# LDR-3.net
KiCad netlist of a schematic drawn in EAGLE
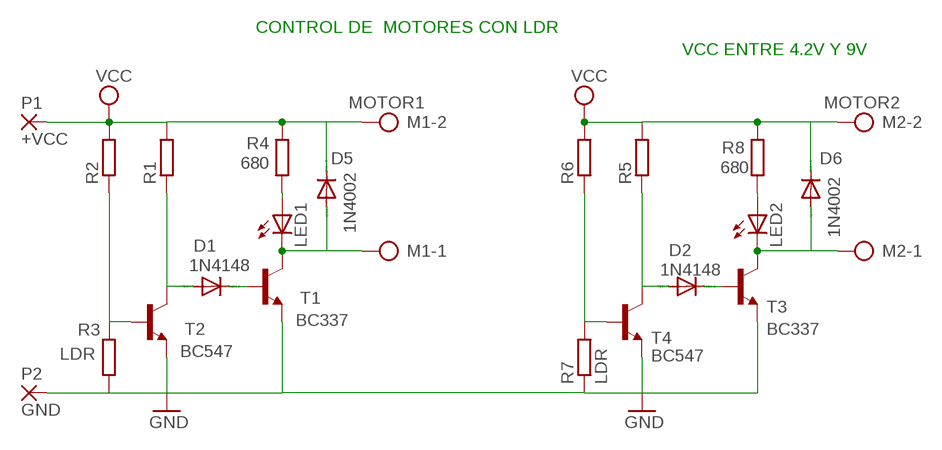
[diagram p0: schematic, sheet 1]

(export (version "E")
  (design (tool "Eeschema 10.0.6"))
  (components
    (comp (ref "D1")
      (value "1N4148")
      (footprint "eagle-import:DO35-7")
      (libsource (lib "eagle-import") (part "1N4148DO35-7"))
    )
    (comp (ref "D2")
      (value "1N4148")
      (footprint "eagle-import:DO35-7")
      (libsource (lib "eagle-import") (part "1N4148DO35-7"))
    )
    (comp (ref "D5")
      (value "1N4002")
      (footprint "eagle-import:DO41-10")
      (libsource (lib "eagle-import") (part "1N4933"))
    )
    (comp (ref "D6")
      (value "1N4002")
      (footprint "eagle-import:DO41-10")
      (libsource (lib "eagle-import") (part "1N4933"))
    )
    (comp (ref "LED1")
      (value "LED3MM")
      (footprint "eagle-import:LED3MM")
      (libsource (lib "eagle-import") (part "LED3MM"))
    )
    (comp (ref "LED2")
      (value "LED3MM")
      (footprint "eagle-import:LED3MM")
      (libsource (lib "eagle-import") (part "LED3MM"))
    )
    (comp (ref "M1")
      (value "MOTOR1")
      (footprint "eagle-import:AK500_2")
      (libsource (lib "eagle-import") (part "AK500/2"))
    )
    (comp (ref "M2")
      (value "MOTOR2")
      (footprint "eagle-import:AK500_2")
      (libsource (lib "eagle-import") (part "AK500/2"))
    )
    (comp (ref "P1")
      (value "+VCC")
      (footprint "eagle-import:2,15_1,0")
      (libsource (lib "eagle-import") (part "WIREPAD2,15/1,0"))
    )
    (comp (ref "P2")
      (value "GND")
      (footprint "eagle-import:2,15_1,0")
      (libsource (lib "eagle-import") (part "WIREPAD2,15/1,0"))
    )
    (comp (ref "R1")
      (value "R-EU_0207/7")
      (footprint "eagle-import:0207_7")
      (libsource (lib "eagle-import") (part "R-EU_0207/7"))
    )
    (comp (ref "R2")
      (value "R-EU_0207/7")
      (footprint "eagle-import:0207_7")
      (libsource (lib "eagle-import") (part "R-EU_0207/7"))
    )
    (comp (ref "R3")
      (value "LDR")
      (footprint "eagle-import:0204_5")
      (libsource (lib "eagle-import") (part "R-EU_0204/5"))
    )
    (comp (ref "R4")
      (value "680")
      (footprint "eagle-import:0207_7")
      (libsource (lib "eagle-import") (part "R-EU_0207/7"))
    )
    (comp (ref "R5")
      (value "R-EU_0207/7")
      (footprint "eagle-import:0207_7")
      (libsource (lib "eagle-import") (part "R-EU_0207/7"))
    )
    (comp (ref "R6")
      (value "R-EU_0207/7")
      (footprint "eagle-import:0207_7")
      (libsource (lib "eagle-import") (part "R-EU_0207/7"))
    )
    (comp (ref "R7")
      (value "LDR")
      (footprint "eagle-import:0204_5")
      (libsource (lib "eagle-import") (part "R-EU_0204/5"))
    )
    (comp (ref "R8")
      (value "680")
      (footprint "eagle-import:0207_7")
      (libsource (lib "eagle-import") (part "R-EU_0207/7"))
    )
    (comp (ref "T1")
      (value "BC337")
      (footprint "eagle-import:TO92-CBE")
      (libsource (lib "eagle-import") (part "-NPN-TO92-CBEBC337-25"))
    )
    (comp (ref "T2")
      (value "BC547")
      (footprint "eagle-import:TO92-CBE")
      (libsource (lib "eagle-import") (part "-NPN-TO92-CBEBC547"))
    )
    (comp (ref "T3")
      (value "BC337")
      (footprint "eagle-import:TO92-CBE")
      (libsource (lib "eagle-import") (part "-NPN-TO92-CBEBC337-25"))
    )
    (comp (ref "T4")
      (value "BC547")
      (footprint "eagle-import:TO92-CBE")
      (libsource (lib "eagle-import") (part "-NPN-TO92-CBEBC547"))
    )
  )
  (nets
    (net (code "1") (name "GND") (class "Default")
      (node (ref "P2") (pin "1") (pinfunction "P_1") (pintype "passive"))
      (node (ref "R3") (pin "1") (pinfunction "1_1") (pintype "passive"))
      (node (ref "R7") (pin "1") (pinfunction "1_1") (pintype "passive"))
      (node (ref "T1") (pin "E") (pinfunction "E_E") (pintype "passive"))
      (node (ref "T2") (pin "E") (pinfunction "E_E") (pintype "passive"))
      (node (ref "T3") (pin "E") (pinfunction "E_E") (pintype "passive"))
      (node (ref "T4") (pin "E") (pinfunction "E_E") (pintype "passive"))
    )
    (net (code "2") (name "Net-(D1-PadA)") (class "Default")
      (node (ref "D1") (pin "A") (pinfunction "A_A") (pintype "passive"))
      (node (ref "R1") (pin "1") (pinfunction "1_1") (pintype "passive"))
      (node (ref "T2") (pin "C") (pinfunction "C_C") (pintype "passive"))
    )
    (net (code "3") (name "Net-(D1-PadC)") (class "Default")
      (node (ref "D1") (pin "C") (pinfunction "C_C") (pintype "passive"))
      (node (ref "T1") (pin "B") (pinfunction "B_B") (pintype "passive"))
    )
    (net (code "4") (name "Net-(D2-PadA)") (class "Default")
      (node (ref "D2") (pin "A") (pinfunction "A_A") (pintype "passive"))
      (node (ref "R5") (pin "1") (pinfunction "1_1") (pintype "passive"))
      (node (ref "T4") (pin "C") (pinfunction "C_C") (pintype "passive"))
    )
    (net (code "5") (name "Net-(D2-PadC)") (class "Default")
      (node (ref "D2") (pin "C") (pinfunction "C_C") (pintype "passive"))
      (node (ref "T3") (pin "B") (pinfunction "B_B") (pintype "passive"))
    )
    (net (code "6") (name "Net-(LED1-C)") (class "Default")
      (node (ref "D5") (pin "A") (pinfunction "A_A") (pintype "passive"))
      (node (ref "LED1") (pin "K") (pinfunction "C_K") (pintype "passive"))
      (node (ref "M1") (pin "1") (pinfunction "KL_1") (pintype "passive"))
      (node (ref "T1") (pin "C") (pinfunction "C_C") (pintype "passive"))
    )
    (net (code "7") (name "Net-(LED1-PadA)") (class "Default")
      (node (ref "LED1") (pin "A") (pinfunction "A_A") (pintype "passive"))
      (node (ref "R4") (pin "1") (pinfunction "1_1") (pintype "passive"))
    )
    (net (code "8") (name "Net-(LED2-C)") (class "Default")
      (node (ref "D6") (pin "A") (pinfunction "A_A") (pintype "passive"))
      (node (ref "LED2") (pin "K") (pinfunction "C_K") (pintype "passive"))
      (node (ref "M2") (pin "1") (pinfunction "KL_1") (pintype "passive"))
      (node (ref "T3") (pin "C") (pinfunction "C_C") (pintype "passive"))
    )
    (net (code "9") (name "Net-(LED2-PadA)") (class "Default")
      (node (ref "LED2") (pin "A") (pinfunction "A_A") (pintype "passive"))
      (node (ref "R8") (pin "1") (pinfunction "1_1") (pintype "passive"))
    )
    (net (code "10") (name "Net-(R2-Pad1)") (class "Default")
      (node (ref "R2") (pin "1") (pinfunction "1_1") (pintype "passive"))
      (node (ref "R3") (pin "2") (pinfunction "2_2") (pintype "passive"))
      (node (ref "T2") (pin "B") (pinfunction "B_B") (pintype "passive"))
    )
    (net (code "11") (name "Net-(R6-Pad1)") (class "Default")
      (node (ref "R6") (pin "1") (pinfunction "1_1") (pintype "passive"))
      (node (ref "R7") (pin "2") (pinfunction "2_2") (pintype "passive"))
      (node (ref "T4") (pin "B") (pinfunction "B_B") (pintype "passive"))
    )
    (net (code "12") (name "VCC") (class "Default")
      (node (ref "D5") (pin "C") (pinfunction "C_C") (pintype "passive"))
      (node (ref "D6") (pin "C") (pinfunction "C_C") (pintype "passive"))
      (node (ref "M1") (pin "2") (pinfunction "KL_2") (pintype "passive"))
      (node (ref "M2") (pin "2") (pinfunction "KL_2") (pintype "passive"))
      (node (ref "P1") (pin "1") (pinfunction "P_1") (pintype "passive"))
      (node (ref "R1") (pin "2") (pinfunction "2_2") (pintype "passive"))
      (node (ref "R2") (pin "2") (pinfunction "2_2") (pintype "passive"))
      (node (ref "R4") (pin "2") (pinfunction "2_2") (pintype "passive"))
      (node (ref "R5") (pin "2") (pinfunction "2_2") (pintype "passive"))
      (node (ref "R6") (pin "2") (pinfunction "2_2") (pintype "passive"))
      (node (ref "R8") (pin "2") (pinfunction "2_2") (pintype "passive"))
    )
  )
)
